# System_critical_signals_PCB.net
KiCad netlist of a schematic drawn in EAGLE
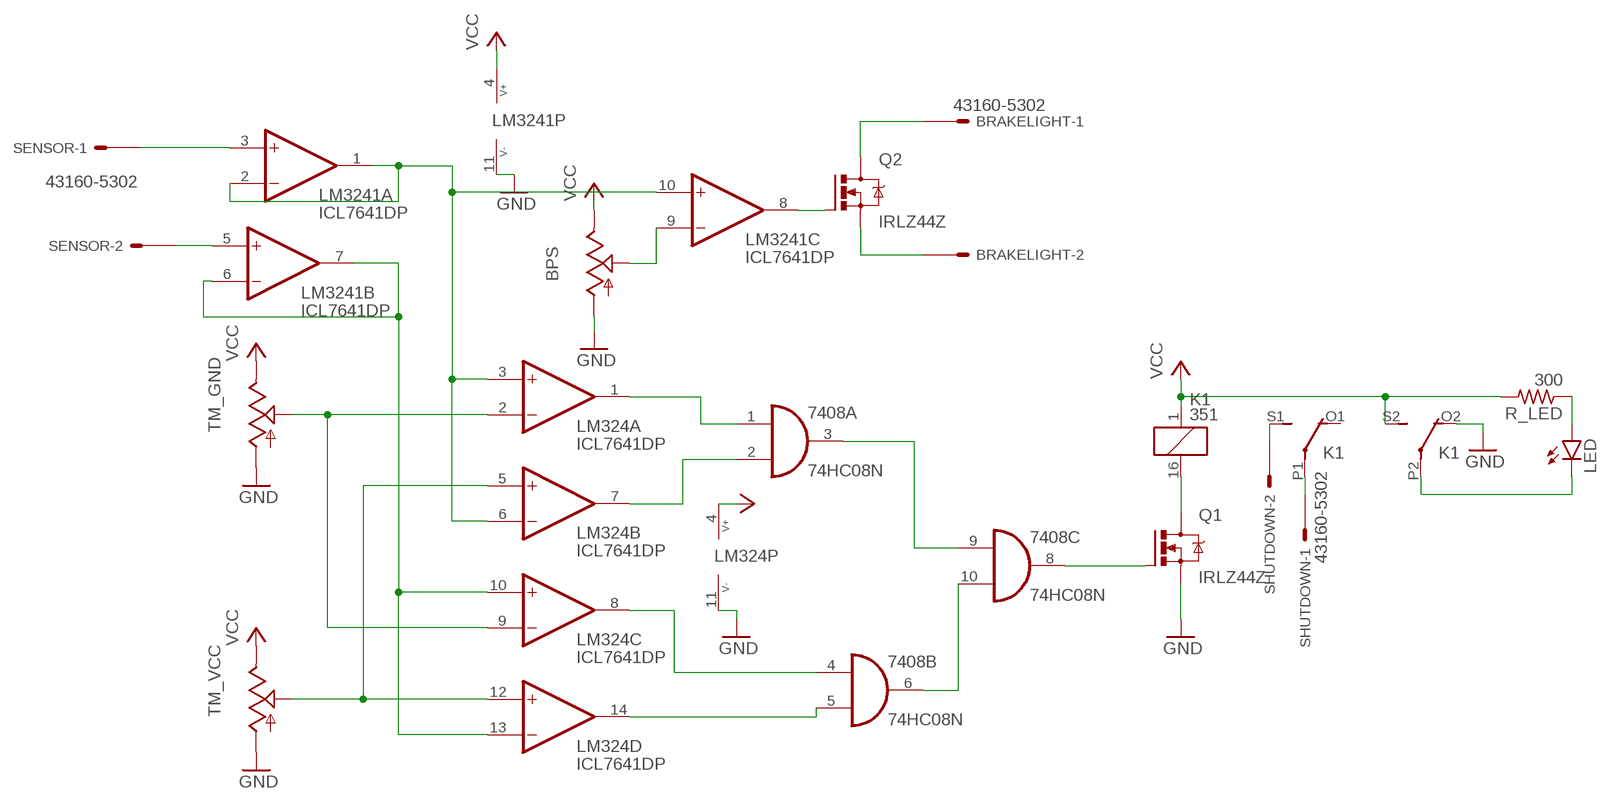
[diagram p0: schematic, sheet 1]

(export (version "E")
  (design (tool "Eeschema 10.0.6"))
  (components
    (comp (ref "7408")
      (value "74HC08N")
      (footprint "eagle-import:DIL14")
      (libsource (lib "eagle-import") (part "7408NHC"))
    )
    (comp (ref "BPS")
      (value "TRIM")
      (footprint "eagle-import:6MM")
      (libsource (lib "eagle-import") (part "TRIM"))
    )
    (comp (ref "BRAKELIGHT")
      (value "43160-5302")
      (footprint "eagle-import:43160-XX02")
      (fields (field (name "MF") "MOLEX"))
      (libsource (lib "eagle-import") (part "43160-0253"))
    )
    (comp (ref "K1")
      (value "351")
      (footprint "eagle-import:351")
      (libsource (lib "eagle-import") (part "351"))
    )
    (comp (ref "LED")
      (value "LEDCHIP-LED0805")
      (footprint "eagle-import:CHIP-LED0805")
      (libsource (lib "eagle-import") (part "LEDCHIP-LED0805"))
    )
    (comp (ref "LM324")
      (value "ICL7641DP")
      (footprint "eagle-import:DIL14")
      (libsource (lib "eagle-import") (part "ICL764DP1"))
    )
    (comp (ref "LM3241")
      (value "ICL7641DP")
      (footprint "eagle-import:DIL14")
      (libsource (lib "eagle-import") (part "ICL764DP1"))
    )
    (comp (ref "Q1")
      (value "IRLZ44Z")
      (footprint "eagle-import:TO220BH")
      (libsource (lib "eagle-import") (part "IRLZ44Z"))
    )
    (comp (ref "Q2")
      (value "IRLZ44Z")
      (footprint "eagle-import:TO220BH")
      (libsource (lib "eagle-import") (part "IRLZ44Z"))
    )
    (comp (ref "R_LED")
      (value "300")
      (footprint "eagle-import:M0805")
      (libsource (lib "eagle-import") (part "R-US_M0805"))
    )
    (comp (ref "SENSOR")
      (value "43160-5302")
      (footprint "eagle-import:43160-XX02")
      (fields (field (name "MF") "MOLEX"))
      (libsource (lib "eagle-import") (part "43160-0253"))
    )
    (comp (ref "SHUTDOWN")
      (value "43160-5302")
      (footprint "eagle-import:43160-XX02")
      (fields (field (name "MF") "MOLEX"))
      (libsource (lib "eagle-import") (part "43160-0253"))
    )
    (comp (ref "TM_GND")
      (value "TRIM")
      (footprint "eagle-import:6MM")
      (libsource (lib "eagle-import") (part "TRIM"))
    )
    (comp (ref "TM_VCC")
      (value "TRIM")
      (footprint "eagle-import:6MM")
      (libsource (lib "eagle-import") (part "TRIM"))
    )
  )
  (nets
    (net (code "1") (name "GND") (class "Default")
      (node (ref "BPS") (pin "A") (pinfunction "A_A") (pintype "passive"))
      (node (ref "K1") (pin "O2") (pinfunction "O_O2") (pintype "passive"))
      (node (ref "LM324") (pin "11") (pinfunction "V-_11") (pintype "power_in"))
      (node (ref "LM3241") (pin "11") (pinfunction "V-_11") (pintype "power_in"))
      (node (ref "Q1") (pin "S") (pinfunction "S_S") (pintype "passive"))
      (node (ref "TM_GND") (pin "A") (pinfunction "A_A") (pintype "passive"))
      (node (ref "TM_VCC") (pin "A") (pinfunction "A_A") (pintype "passive"))
    )
    (net (code "2") (name "Net-(7408A-I0)") (class "Default")
      (node (ref "7408") (pin "1") (pinfunction "I0_1") (pintype "input"))
      (node (ref "LM324") (pin "1") (pinfunction "OUT_1") (pintype "output"))
    )
    (net (code "3") (name "Net-(7408A-I1)") (class "Default")
      (node (ref "7408") (pin "2") (pinfunction "I1_2") (pintype "input"))
      (node (ref "LM324") (pin "7") (pinfunction "OUT_7") (pintype "output"))
    )
    (net (code "4") (name "Net-(7408A-O)") (class "Default")
      (node (ref "7408") (pin "3") (pinfunction "O_3") (pintype "output"))
      (node (ref "7408") (pin "9") (pinfunction "I0_9") (pintype "input"))
    )
    (net (code "5") (name "Net-(7408B-I0)") (class "Default")
      (node (ref "7408") (pin "4") (pinfunction "I0_4") (pintype "input"))
      (node (ref "LM324") (pin "8") (pinfunction "OUT_8") (pintype "output"))
    )
    (net (code "6") (name "Net-(7408B-I1)") (class "Default")
      (node (ref "7408") (pin "5") (pinfunction "I1_5") (pintype "input"))
      (node (ref "LM324") (pin "14") (pinfunction "OUT_14") (pintype "output"))
    )
    (net (code "7") (name "Net-(7408B-O)") (class "Default")
      (node (ref "7408") (pin "10") (pinfunction "I1_10") (pintype "input"))
      (node (ref "7408") (pin "6") (pinfunction "O_6") (pintype "output"))
    )
    (net (code "8") (name "Net-(7408C-O)") (class "Default")
      (node (ref "7408") (pin "8") (pinfunction "O_8") (pintype "output"))
      (node (ref "Q1") (pin "G") (pinfunction "G_G") (pintype "passive"))
    )
    (net (code "9") (name "Net-(BRAKELIGHTA-S-Pad1@1)") (class "Default")
      (node (ref "BRAKELIGHT") (pin "1@1") (pinfunction "S_1@1") (pintype "passive"))
      (node (ref "Q2") (pin "D") (pinfunction "D_D") (pintype "passive"))
    )
    (net (code "10") (name "Net-(BRAKELIGHTB-S-Pad2@1)") (class "Default")
      (node (ref "BRAKELIGHT") (pin "2@1") (pinfunction "S_2@1") (pintype "passive"))
      (node (ref "Q2") (pin "S") (pinfunction "S_S") (pintype "passive"))
    )
    (net (code "11") (name "Net-(K1A-2)") (class "Default")
      (node (ref "K1") (pin "16") (pinfunction "2_16") (pintype "passive"))
      (node (ref "Q1") (pin "D") (pinfunction "D_D") (pintype "passive"))
    )
    (net (code "12") (name "Net-(K1B-P)") (class "Default")
      (node (ref "K1") (pin "P1") (pinfunction "P_P1") (pintype "passive"))
      (node (ref "SHUTDOWN") (pin "1@1") (pinfunction "S_1@1") (pintype "passive"))
    )
    (net (code "13") (name "Net-(K1B-S)") (class "Default")
      (node (ref "K1") (pin "S1") (pinfunction "S_S1") (pintype "passive"))
      (node (ref "SHUTDOWN") (pin "2@1") (pinfunction "S_2@1") (pintype "passive"))
    )
    (net (code "14") (name "Net-(K1C-P)") (class "Default")
      (node (ref "K1") (pin "P2") (pinfunction "P_P2") (pintype "passive"))
      (node (ref "LED") (pin "C") (pinfunction "C_C") (pintype "passive"))
    )
    (net (code "15") (name "Net-(LED-PadA)") (class "Default")
      (node (ref "LED") (pin "A") (pinfunction "A_A") (pintype "passive"))
      (node (ref "R_LED") (pin "1") (pinfunction "1_1") (pintype "passive"))
    )
    (net (code "16") (name "Net-(LM324A--IN)") (class "Default")
      (node (ref "LM324") (pin "2") (pinfunction "-IN_2") (pintype "input"))
      (node (ref "LM324") (pin "9") (pinfunction "-IN_9") (pintype "input"))
      (node (ref "TM_GND") (pin "S") (pinfunction "S_S") (pintype "passive"))
    )
    (net (code "17") (name "Net-(LM324B-+IN)") (class "Default")
      (node (ref "LM324") (pin "12") (pinfunction "+IN_12") (pintype "input"))
      (node (ref "LM324") (pin "5") (pinfunction "+IN_5") (pintype "input"))
      (node (ref "TM_VCC") (pin "S") (pinfunction "S_S") (pintype "passive"))
    )
    (net (code "18") (name "Net-(LM3241A-+IN)") (class "Default")
      (node (ref "LM3241") (pin "3") (pinfunction "+IN_3") (pintype "input"))
      (node (ref "SENSOR") (pin "1@1") (pinfunction "S_1@1") (pintype "passive"))
    )
    (net (code "19") (name "Net-(LM3241A--IN)") (class "Default")
      (node (ref "LM324") (pin "3") (pinfunction "+IN_3") (pintype "input"))
      (node (ref "LM324") (pin "6") (pinfunction "-IN_6") (pintype "input"))
      (node (ref "LM3241") (pin "1") (pinfunction "OUT_1") (pintype "output"))
      (node (ref "LM3241") (pin "10") (pinfunction "+IN_10") (pintype "input"))
      (node (ref "LM3241") (pin "2") (pinfunction "-IN_2") (pintype "input"))
    )
    (net (code "20") (name "Net-(LM3241B-+IN)") (class "Default")
      (node (ref "LM3241") (pin "5") (pinfunction "+IN_5") (pintype "input"))
      (node (ref "SENSOR") (pin "2@1") (pinfunction "S_2@1") (pintype "passive"))
    )
    (net (code "21") (name "Net-(LM3241B--IN)") (class "Default")
      (node (ref "LM324") (pin "10") (pinfunction "+IN_10") (pintype "input"))
      (node (ref "LM324") (pin "13") (pinfunction "-IN_13") (pintype "input"))
      (node (ref "LM3241") (pin "6") (pinfunction "-IN_6") (pintype "input"))
      (node (ref "LM3241") (pin "7") (pinfunction "OUT_7") (pintype "output"))
    )
    (net (code "22") (name "Net-(LM3241C--IN)") (class "Default")
      (node (ref "BPS") (pin "S") (pinfunction "S_S") (pintype "passive"))
      (node (ref "LM3241") (pin "9") (pinfunction "-IN_9") (pintype "input"))
    )
    (net (code "23") (name "Net-(LM3241C-OUT)") (class "Default")
      (node (ref "LM3241") (pin "8") (pinfunction "OUT_8") (pintype "output"))
      (node (ref "Q2") (pin "G") (pinfunction "G_G") (pintype "passive"))
    )
    (net (code "24") (name "VCC") (class "Default")
      (node (ref "BPS") (pin "E") (pinfunction "E_E") (pintype "passive"))
      (node (ref "K1") (pin "1") (pinfunction "1_1") (pintype "passive"))
      (node (ref "K1") (pin "S2") (pinfunction "S_S2") (pintype "passive"))
      (node (ref "LM324") (pin "4") (pinfunction "V+_4") (pintype "power_in"))
      (node (ref "LM3241") (pin "4") (pinfunction "V+_4") (pintype "power_in"))
      (node (ref "R_LED") (pin "2") (pinfunction "2_2") (pintype "passive"))
      (node (ref "TM_GND") (pin "E") (pinfunction "E_E") (pintype "passive"))
      (node (ref "TM_VCC") (pin "E") (pinfunction "E_E") (pintype "passive"))
    )
    (net (code "25") (name "unconnected-(BRAKELIGHTA-S-Pad1@2)") (class "Default")
      (node (ref "BRAKELIGHT") (pin "1@2") (pinfunction "S_1@2") (pintype "passive"))
    )
    (net (code "26") (name "unconnected-(BRAKELIGHTB-S-Pad2@2)") (class "Default")
      (node (ref "BRAKELIGHT") (pin "2@2") (pinfunction "S_2@2") (pintype "passive"))
    )
    (net (code "27") (name "unconnected-(K1B-O-PadO1)") (class "Default")
      (node (ref "K1") (pin "O1") (pinfunction "O_O1") (pintype "passive"))
    )
    (net (code "28") (name "unconnected-(SENSORA-S-Pad1@2)") (class "Default")
      (node (ref "SENSOR") (pin "1@2") (pinfunction "S_1@2") (pintype "passive"))
    )
    (net (code "29") (name "unconnected-(SENSORB-S-Pad2@2)") (class "Default")
      (node (ref "SENSOR") (pin "2@2") (pinfunction "S_2@2") (pintype "passive"))
    )
    (net (code "30") (name "unconnected-(SHUTDOWNA-S-Pad1@2)") (class "Default")
      (node (ref "SHUTDOWN") (pin "1@2") (pinfunction "S_1@2") (pintype "passive"))
    )
    (net (code "31") (name "unconnected-(SHUTDOWNB-S-Pad2@2)") (class "Default")
      (node (ref "SHUTDOWN") (pin "2@2") (pinfunction "S_2@2") (pintype "passive"))
    )
  )
)
